# GPS_radiologger_v21_L70_CMWX.net
KiCad netlist of a schematic drawn in EAGLE
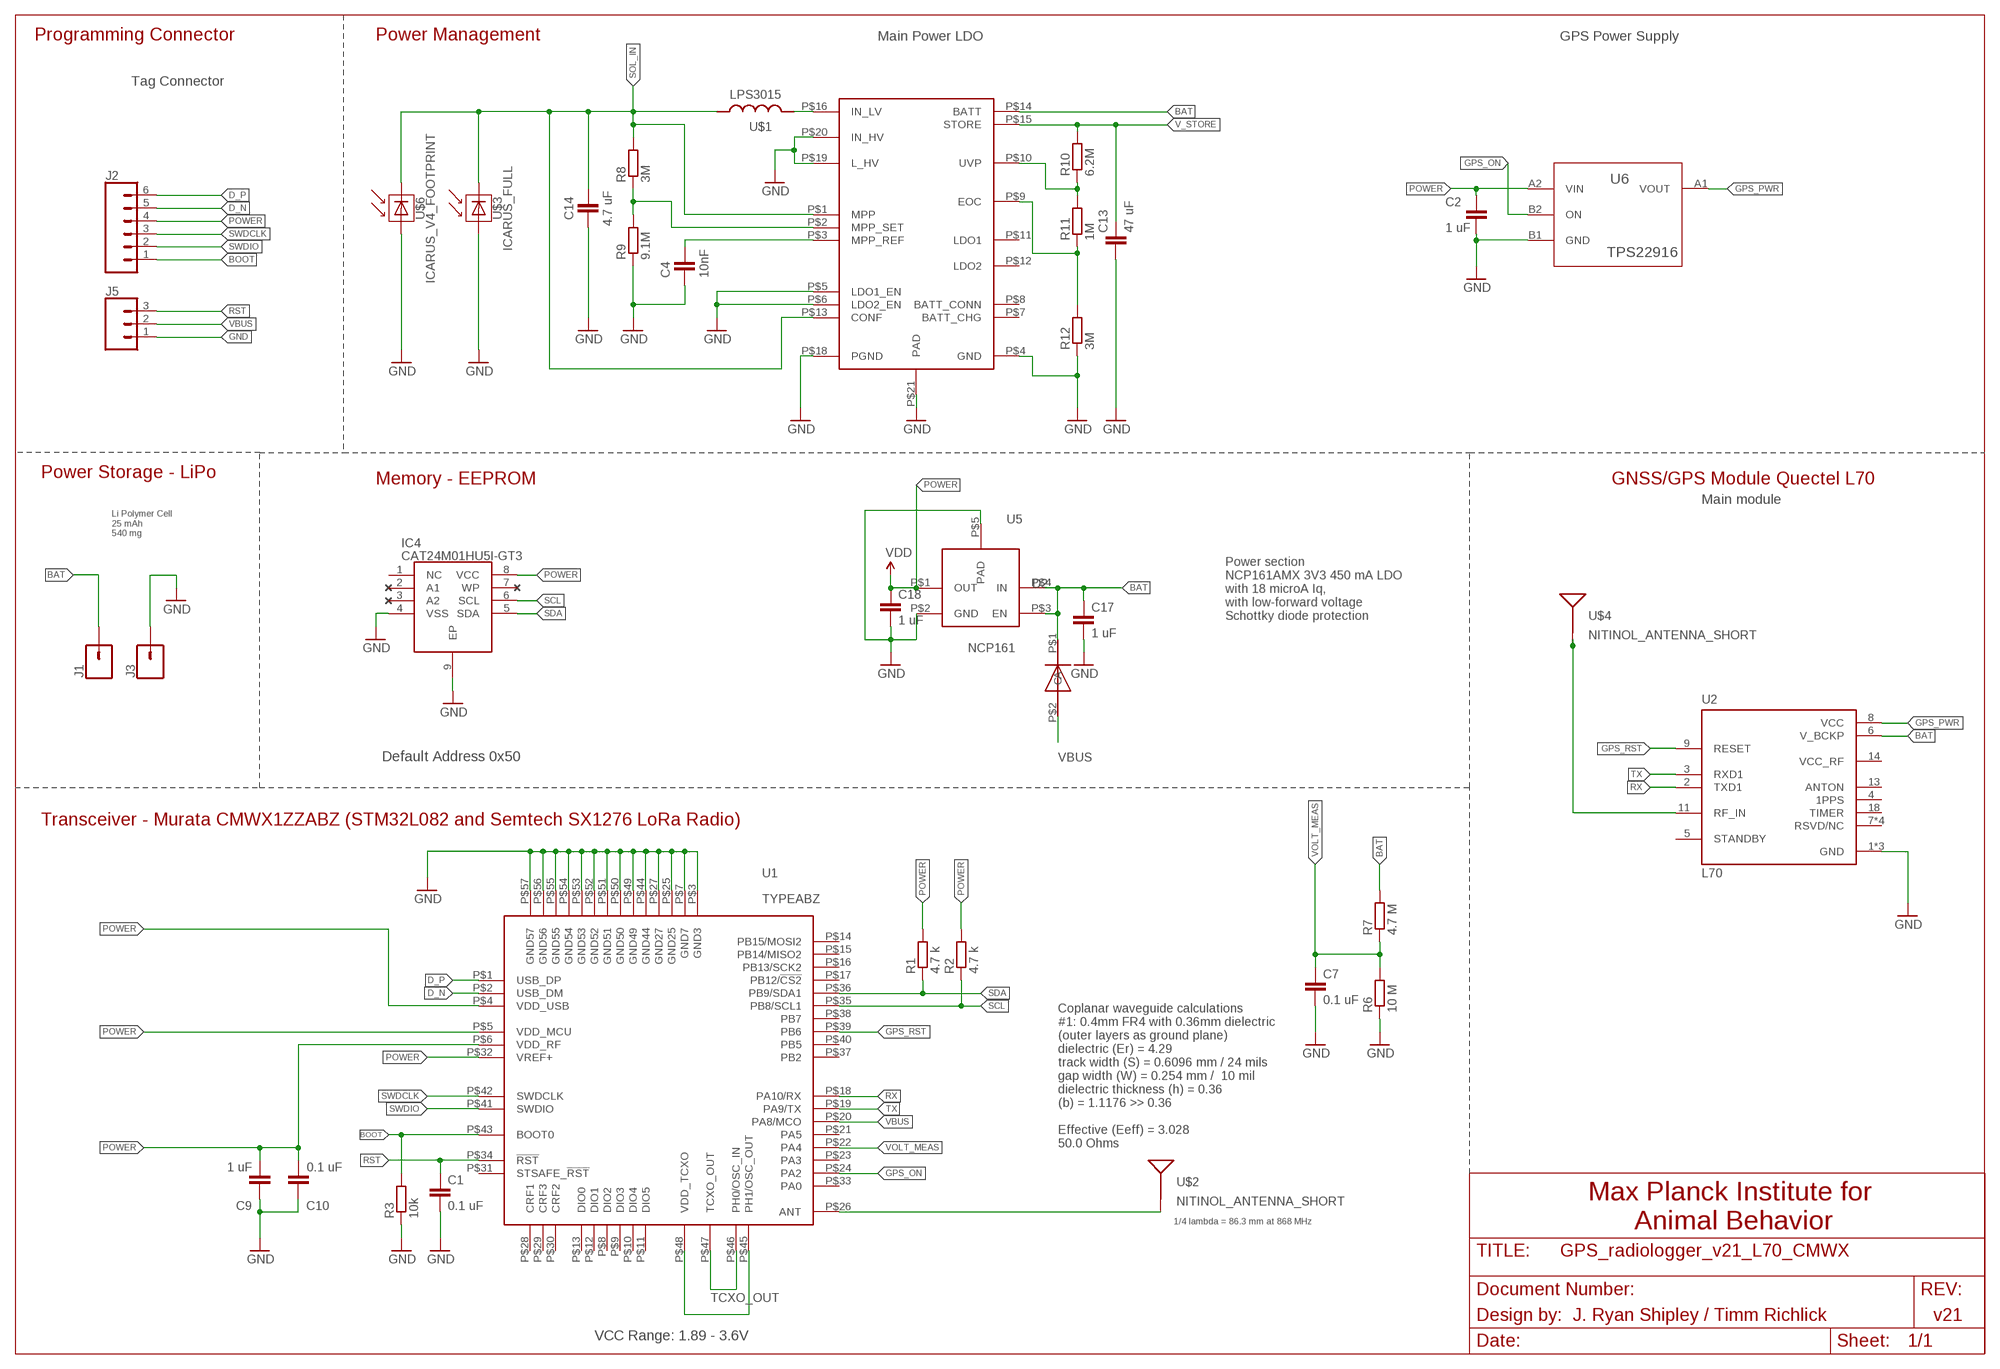
[diagram p0: schematic, sheet 1]

(export (version "E")
  (design (tool "Eeschema 10.0.6"))
  (components
    (comp (ref "C1")
      (value "0.1 uF")
      (footprint "eagle-import:C0201")
      (libsource (lib "eagle-import") (part "C-EUC0201"))
    )
    (comp (ref "C2")
      (value "1 uF")
      (footprint "eagle-import:C0201")
      (libsource (lib "eagle-import") (part "C-EUC0201"))
    )
    (comp (ref "C4")
      (value "10nF")
      (footprint "eagle-import:C0201")
      (libsource (lib "eagle-import") (part "C-EUC0201"))
    )
    (comp (ref "C7")
      (value "0.1 uF")
      (footprint "eagle-import:C0201")
      (libsource (lib "eagle-import") (part "C-EUC0201"))
    )
    (comp (ref "C9")
      (value "1 uF")
      (footprint "eagle-import:C0201")
      (libsource (lib "eagle-import") (part "C-EUC0201"))
    )
    (comp (ref "C10")
      (value "0.1 uF")
      (footprint "eagle-import:C0201")
      (libsource (lib "eagle-import") (part "C-EUC0201"))
    )
    (comp (ref "C13")
      (value "47 uF")
      (footprint "eagle-import:C0603")
      (libsource (lib "eagle-import") (part "C-EUC0603"))
    )
    (comp (ref "C14")
      (value "4.7 uF")
      (footprint "eagle-import:C0201")
      (libsource (lib "eagle-import") (part "C-EUC0201"))
    )
    (comp (ref "C17")
      (value "1 uF")
      (footprint "eagle-import:0402-CAP")
      (libsource (lib "eagle-import") (part "0402CAP.KW"))
    )
    (comp (ref "C18")
      (value "1 uF")
      (footprint "eagle-import:0402-CAP")
      (libsource (lib "eagle-import") (part "0402CAP.KW"))
    )
    (comp (ref "D2")
      (value "CDSQR4148-HF")
      (footprint "eagle-import:CDSQR4148-HF")
      (libsource (lib "eagle-import") (part "CDSQR4148-HF"))
    )
    (comp (ref "IC4")
      (value "CAT24M01HU5I-GT3")
      (footprint "eagle-import:SON50P300X200X55-9N")
      (fields
        (field (name "MOUSER_PART_NUMBER") "863-CAT24M01HU5I-GT3")
        (field (name "RS_PART_NUMBER") "7814831P")
      )
      (libsource (lib "eagle-import") (part "CAT24M01HU5I-GT3"))
    )
    (comp (ref "J1")
      (value "CONN_01PTH_NO_SILK_SMALL")
      (footprint "eagle-import:1X01_SMALL")
      (libsource (lib "eagle-import") (part "CONN_01PTH_NO_SILK_SMALL"))
    )
    (comp (ref "J2")
      (value "CONN_061.27MM")
      (footprint "eagle-import:1X06_1.27MM")
      (libsource (lib "eagle-import") (part "CONN_061.27MM"))
    )
    (comp (ref "J3")
      (value "CONN_01PTH_NO_SILK_SMALL")
      (footprint "eagle-import:1X01_SMALL")
      (libsource (lib "eagle-import") (part "CONN_01PTH_NO_SILK_SMALL"))
    )
    (comp (ref "J5")
      (value "CONN_031X03_1.27_NO_SILK")
      (footprint "eagle-import:1X03_1.27MM_NO_SILK")
      (libsource (lib "eagle-import") (part "CONN_031X03_1.27_NO_SILK"))
    )
    (comp (ref "R1")
      (value "4.7 k")
      (footprint "eagle-import:R0201")
      (libsource (lib "eagle-import") (part "R-EU_R0201"))
    )
    (comp (ref "R2")
      (value "4.7 k")
      (footprint "eagle-import:R0201")
      (libsource (lib "eagle-import") (part "R-EU_R0201"))
    )
    (comp (ref "R3")
      (value "10k")
      (footprint "eagle-import:R0201")
      (libsource (lib "eagle-import") (part "R-EU_R0201"))
    )
    (comp (ref "R6")
      (value "10 M")
      (footprint "eagle-import:R0201")
      (libsource (lib "eagle-import") (part "R-EU_R0201"))
    )
    (comp (ref "R7")
      (value "4.7 M")
      (footprint "eagle-import:R0201")
      (libsource (lib "eagle-import") (part "R-EU_R0201"))
    )
    (comp (ref "R8")
      (value "3M")
      (footprint "eagle-import:R0201")
      (libsource (lib "eagle-import") (part "R-EU_R0201"))
    )
    (comp (ref "R9")
      (value "9.1M")
      (footprint "eagle-import:R0201")
      (libsource (lib "eagle-import") (part "R-EU_R0201"))
    )
    (comp (ref "R10")
      (value "6.2M")
      (footprint "eagle-import:R0201")
      (libsource (lib "eagle-import") (part "R-EU_R0201"))
    )
    (comp (ref "R11")
      (value "1M")
      (footprint "eagle-import:R0201")
      (libsource (lib "eagle-import") (part "R-EU_R0201"))
    )
    (comp (ref "R12")
      (value "3M")
      (footprint "eagle-import:R0201")
      (libsource (lib "eagle-import") (part "R-EU_R0201"))
    )
    (comp (ref "U$1")
      (value "LPS3015")
      (footprint "eagle-import:LPS_3015")
      (libsource (lib "eagle-import") (part "LPS3015"))
    )
    (comp (ref "U$2")
      (value "NITINOL_ANTENNA_SHORT")
      (footprint "eagle-import:ICARUS_NITINOL_ANTENNA_SHORT")
      (libsource (lib "eagle-import") (part "NITINOL_ANTENNA_SHORT"))
    )
    (comp (ref "U$3")
      (value "ICARUS_FULL")
      (footprint "eagle-import:ICARUS_FULL")
      (libsource (lib "eagle-import") (part "ICARUS_FULL"))
    )
    (comp (ref "U$4")
      (value "NITINOL_ANTENNA_SHORT")
      (footprint "eagle-import:ICARUS_NITINOL_ANTENNA_SHORT")
      (libsource (lib "eagle-import") (part "NITINOL_ANTENNA_SHORT"))
    )
    (comp (ref "U$6")
      (value "ICARUS_V4_FOOTPRINT")
      (footprint "eagle-import:ICARUS_FULL_FOOTPRINT")
      (libsource (lib "eagle-import") (part "ICARUS_V4_FOOTPRINT"))
    )
    (comp (ref "U1")
      (value "TYPEABZ")
      (footprint "eagle-import:TYPEABZ")
      (libsource (lib "eagle-import") (part "TYPEABZ"))
    )
    (comp (ref "U2")
      (value "L70")
      (footprint "eagle-import:XCVR_L70")
      (fields (field (name "MF") "Quectel"))
      (libsource (lib "eagle-import") (part "L70"))
    )
    (comp (ref "U4")
      (value "SPV1050")
      (footprint "eagle-import:SPV1050")
      (libsource (lib "eagle-import") (part "SPV1050"))
    )
    (comp (ref "U5")
      (value "NCP161")
      (footprint "eagle-import:NCP161")
      (libsource (lib "eagle-import") (part "NCP161"))
    )
    (comp (ref "U6")
      (value "TPS22916")
      (footprint "eagle-import:TPS22916")
      (fields (field (name "MF") "Texas Instruments") (field (name "MP") "LP5900TL-3.0"))
      (libsource (lib "eagle-import") (part "TPS22916"))
    )
  )
  (nets
    (net (code "1") (name "/TCXO_OUT") (class "Default")
      (node (ref "U1") (pin "P$46") (pinfunction "PH0/OSC_IN_P$46") (pintype "bidirectional"))
      (node (ref "U1") (pin "P$47") (pinfunction "TCXO_OUT_P$47") (pintype "bidirectional"))
    )
    (net (code "2") (name "BAT") (class "Default")
      (node (ref "C17") (pin "1") (pinfunction "1_1") (pintype "passive"))
      (node (ref "D2") (pin "P$1") (pinfunction "C_P$1") (pintype "bidirectional"))
      (node (ref "J1") (pin "P$1") (pinfunction "1_P$1") (pintype "passive"))
      (node (ref "R7") (pin "2") (pinfunction "2_2") (pintype "passive"))
      (node (ref "U2") (pin "6") (pinfunction "V_BCKP_6") (pintype "power_in"))
      (node (ref "U4") (pin "P$14") (pinfunction "BATT_P$14") (pintype "bidirectional"))
      (node (ref "U5") (pin "P$3") (pinfunction "EN_P$3") (pintype "bidirectional"))
      (node (ref "U5") (pin "P$4") (pinfunction "IN_P$4") (pintype "power_in"))
    )
    (net (code "3") (name "BOOT") (class "Default")
      (node (ref "J2") (pin "1") (pinfunction "1_1") (pintype "passive"))
      (node (ref "R3") (pin "2") (pinfunction "2_2") (pintype "passive"))
      (node (ref "U1") (pin "P$43") (pinfunction "BOOT0_P$43") (pintype "bidirectional"))
    )
    (net (code "4") (name "D_N") (class "Default")
      (node (ref "J2") (pin "5") (pinfunction "5_5") (pintype "passive"))
      (node (ref "U1") (pin "P$2") (pinfunction "USB_DM_P$2") (pintype "bidirectional"))
    )
    (net (code "5") (name "D_P") (class "Default")
      (node (ref "J2") (pin "6") (pinfunction "6_6") (pintype "passive"))
      (node (ref "U1") (pin "P$1") (pinfunction "USB_DP_P$1") (pintype "bidirectional"))
    )
    (net (code "6") (name "GND") (class "Default")
      (node (ref "C1") (pin "2") (pinfunction "2_2") (pintype "passive"))
      (node (ref "C10") (pin "1") (pinfunction "1_1") (pintype "passive"))
      (node (ref "C13") (pin "2") (pinfunction "2_2") (pintype "passive"))
      (node (ref "C14") (pin "2") (pinfunction "2_2") (pintype "passive"))
      (node (ref "C17") (pin "2") (pinfunction "2_2") (pintype "passive"))
      (node (ref "C18") (pin "2") (pinfunction "2_2") (pintype "passive"))
      (node (ref "C2") (pin "2") (pinfunction "2_2") (pintype "passive"))
      (node (ref "C4") (pin "2") (pinfunction "2_2") (pintype "passive"))
      (node (ref "C7") (pin "2") (pinfunction "2_2") (pintype "passive"))
      (node (ref "C9") (pin "1") (pinfunction "1_1") (pintype "passive"))
      (node (ref "IC4") (pin "4") (pinfunction "VSS_4") (pintype "power_in"))
      (node (ref "IC4") (pin "9") (pinfunction "EP_9") (pintype "bidirectional"))
      (node (ref "J3") (pin "P$1") (pinfunction "1_P$1") (pintype "passive"))
      (node (ref "J5") (pin "1") (pinfunction "1_1") (pintype "passive"))
      (node (ref "R12") (pin "1") (pinfunction "1_1") (pintype "passive"))
      (node (ref "R3") (pin "1") (pinfunction "1_1") (pintype "passive"))
      (node (ref "R6") (pin "1") (pinfunction "1_1") (pintype "passive"))
      (node (ref "R9") (pin "1") (pinfunction "1_1") (pintype "passive"))
      (node (ref "U$3") (pin "P$2") (pinfunction "MINUS_P$2") (pintype "passive"))
      (node (ref "U$6") (pin "P$3") (pinfunction "MINUS_P$3") (pintype "passive"))
      (node (ref "U1") (pin "P$25") (pinfunction "GND25_P$25") (pintype "power_in"))
      (node (ref "U1") (pin "P$27") (pinfunction "GND27_P$27") (pintype "power_in"))
      (node (ref "U1") (pin "P$3") (pinfunction "GND3_P$3") (pintype "power_in"))
      (node (ref "U1") (pin "P$44") (pinfunction "GND44_P$44") (pintype "power_in"))
      (node (ref "U1") (pin "P$49") (pinfunction "GND49_P$49") (pintype "power_in"))
      (node (ref "U1") (pin "P$50") (pinfunction "GND50_P$50") (pintype "power_in"))
      (node (ref "U1") (pin "P$51") (pinfunction "GND51_P$51") (pintype "power_in"))
      (node (ref "U1") (pin "P$52") (pinfunction "GND52_P$52") (pintype "power_in"))
      (node (ref "U1") (pin "P$53") (pinfunction "GND53_P$53") (pintype "power_in"))
      (node (ref "U1") (pin "P$54") (pinfunction "GND54_P$54") (pintype "power_in"))
      (node (ref "U1") (pin "P$55") (pinfunction "GND55_P$55") (pintype "power_in"))
      (node (ref "U1") (pin "P$56") (pinfunction "GND56_P$56") (pintype "power_in"))
      (node (ref "U1") (pin "P$57") (pinfunction "GND57_P$57") (pintype "power_in"))
      (node (ref "U1") (pin "P$7") (pinfunction "GND7_P$7") (pintype "power_in"))
      (node (ref "U2") (pin "1") (pinfunction "GND_1") (pintype "power_in"))
      (node (ref "U2") (pin "10") (pinfunction "GND_10") (pintype "power_in"))
      (node (ref "U2") (pin "12") (pinfunction "GND_12") (pintype "power_in"))
      (node (ref "U4") (pin "P$18") (pinfunction "PGND_P$18") (pintype "power_in"))
      (node (ref "U4") (pin "P$19") (pinfunction "L_HV_P$19") (pintype "power_in"))
      (node (ref "U4") (pin "P$20") (pinfunction "IN_HV_P$20") (pintype "power_in"))
      (node (ref "U4") (pin "P$21") (pinfunction "PAD_P$21") (pintype "power_in"))
      (node (ref "U4") (pin "P$4") (pinfunction "GND_P$4") (pintype "power_in"))
      (node (ref "U4") (pin "P$5") (pinfunction "LDO1_EN_P$5") (pintype "input"))
      (node (ref "U4") (pin "P$6") (pinfunction "LDO2_EN_P$6") (pintype "input"))
      (node (ref "U5") (pin "P$2") (pinfunction "GND_P$2") (pintype "power_in"))
      (node (ref "U5") (pin "P$5") (pinfunction "PAD_P$5") (pintype "power_in"))
      (node (ref "U6") (pin "B1") (pinfunction "GND_B1") (pintype "passive"))
    )
    (net (code "7") (name "GPS_ON") (class "Default")
      (node (ref "U1") (pin "P$24") (pinfunction "PA2_P$24") (pintype "bidirectional"))
      (node (ref "U6") (pin "B2") (pinfunction "ON_B2") (pintype "input"))
    )
    (net (code "8") (name "GPS_PWR") (class "Default")
      (node (ref "U2") (pin "8") (pinfunction "VCC_8") (pintype "power_in"))
      (node (ref "U6") (pin "A1") (pinfunction "VOUT_A1") (pintype "output"))
    )
    (net (code "9") (name "GPS_RST") (class "Default")
      (node (ref "U1") (pin "P$39") (pinfunction "PB6_P$39") (pintype "bidirectional"))
      (node (ref "U2") (pin "9") (pinfunction "RESET_9") (pintype "input"))
    )
    (net (code "10") (name "Net-(U$1-2)") (class "Default")
      (node (ref "U$1") (pin "P$2") (pinfunction "2_P$2") (pintype "passive"))
      (node (ref "U4") (pin "P$16") (pinfunction "IN_LV_P$16") (pintype "power_in"))
    )
    (net (code "11") (name "Net-(U1-ANT)") (class "Default")
      (node (ref "U$2") (pin "1") (pinfunction "SIGNAL_1") (pintype "bidirectional"))
      (node (ref "U$2") (pin "2") (pinfunction "SIGNAL_2") (pintype "bidirectional"))
      (node (ref "U$2") (pin "3") (pinfunction "SIGNAL_3") (pintype "bidirectional"))
      (node (ref "U1") (pin "P$26") (pinfunction "ANT_P$26") (pintype "bidirectional"))
    )
    (net (code "12") (name "Net-(U1-PH1{slash}OSC_OUT)") (class "Default")
      (node (ref "U1") (pin "P$45") (pinfunction "PH1/OSC_OUT_P$45") (pintype "bidirectional"))
      (node (ref "U1") (pin "P$48") (pinfunction "VDD_TCXO_P$48") (pintype "power_in"))
    )
    (net (code "13") (name "Net-(U2-RF_IN)") (class "Default")
      (node (ref "U$4") (pin "1") (pinfunction "SIGNAL_1") (pintype "bidirectional"))
      (node (ref "U$4") (pin "2") (pinfunction "SIGNAL_2") (pintype "bidirectional"))
      (node (ref "U$4") (pin "3") (pinfunction "SIGNAL_3") (pintype "bidirectional"))
      (node (ref "U2") (pin "11") (pinfunction "RF_IN_11") (pintype "input"))
    )
    (net (code "14") (name "Net-(U4-EOC)") (class "Default")
      (node (ref "R11") (pin "1") (pinfunction "1_1") (pintype "passive"))
      (node (ref "R12") (pin "2") (pinfunction "2_2") (pintype "passive"))
      (node (ref "U4") (pin "P$9") (pinfunction "EOC_P$9") (pintype "input"))
    )
    (net (code "15") (name "Net-(U4-MPP_REF)") (class "Default")
      (node (ref "C4") (pin "1") (pinfunction "1_1") (pintype "passive"))
      (node (ref "U4") (pin "P$3") (pinfunction "MPP_REF_P$3") (pintype "input"))
    )
    (net (code "16") (name "Net-(U4-MPP_SET)") (class "Default")
      (node (ref "R8") (pin "1") (pinfunction "1_1") (pintype "passive"))
      (node (ref "R9") (pin "2") (pinfunction "2_2") (pintype "passive"))
      (node (ref "U4") (pin "P$2") (pinfunction "MPP_SET_P$2") (pintype "input"))
    )
    (net (code "17") (name "Net-(U4-UVP)") (class "Default")
      (node (ref "R10") (pin "1") (pinfunction "1_1") (pintype "passive"))
      (node (ref "R11") (pin "2") (pinfunction "2_2") (pintype "passive"))
      (node (ref "U4") (pin "P$10") (pinfunction "UVP_P$10") (pintype "input"))
    )
    (net (code "18") (name "POWER") (class "Default")
      (node (ref "C10") (pin "2") (pinfunction "2_2") (pintype "passive"))
      (node (ref "C18") (pin "1") (pinfunction "1_1") (pintype "passive"))
      (node (ref "C2") (pin "1") (pinfunction "1_1") (pintype "passive"))
      (node (ref "C9") (pin "2") (pinfunction "2_2") (pintype "passive"))
      (node (ref "IC4") (pin "8") (pinfunction "VCC_8") (pintype "power_in"))
      (node (ref "J2") (pin "4") (pinfunction "4_4") (pintype "passive"))
      (node (ref "R1") (pin "2") (pinfunction "2_2") (pintype "passive"))
      (node (ref "R2") (pin "2") (pinfunction "2_2") (pintype "passive"))
      (node (ref "U1") (pin "P$32") (pinfunction "VREF+_P$32") (pintype "power_in"))
      (node (ref "U1") (pin "P$4") (pinfunction "VDD_USB_P$4") (pintype "power_in"))
      (node (ref "U1") (pin "P$5") (pinfunction "VDD_MCU_P$5") (pintype "power_in"))
      (node (ref "U1") (pin "P$6") (pinfunction "VDD_RF_P$6") (pintype "power_in"))
      (node (ref "U5") (pin "P$1") (pinfunction "OUT_P$1") (pintype "power_in"))
      (node (ref "U6") (pin "A2") (pinfunction "VIN_A2") (pintype "power_in"))
    )
    (net (code "19") (name "RST") (class "Default")
      (node (ref "C1") (pin "1") (pinfunction "1_1") (pintype "passive"))
      (node (ref "J5") (pin "3") (pinfunction "3_3") (pintype "passive"))
      (node (ref "U1") (pin "P$34") (pinfunction "~{RST}_P$34") (pintype "bidirectional"))
    )
    (net (code "20") (name "RX") (class "Default")
      (node (ref "U1") (pin "P$18") (pinfunction "PA10/RX_P$18") (pintype "bidirectional"))
      (node (ref "U2") (pin "2") (pinfunction "TXD1_2") (pintype "output"))
    )
    (net (code "21") (name "SCL") (class "Default")
      (node (ref "IC4") (pin "6") (pinfunction "SCL_6") (pintype "bidirectional"))
      (node (ref "R2") (pin "1") (pinfunction "1_1") (pintype "passive"))
      (node (ref "U1") (pin "P$35") (pinfunction "PB8/SCL1_P$35") (pintype "bidirectional"))
    )
    (net (code "22") (name "SDA") (class "Default")
      (node (ref "IC4") (pin "5") (pinfunction "SDA_5") (pintype "bidirectional"))
      (node (ref "R1") (pin "1") (pinfunction "1_1") (pintype "passive"))
      (node (ref "U1") (pin "P$36") (pinfunction "PB9/SDA1_P$36") (pintype "bidirectional"))
    )
    (net (code "23") (name "SOL_IN") (class "Default")
      (node (ref "C14") (pin "1") (pinfunction "1_1") (pintype "passive"))
      (node (ref "R8") (pin "2") (pinfunction "2_2") (pintype "passive"))
      (node (ref "U$1") (pin "P$1") (pinfunction "1_P$1") (pintype "passive"))
      (node (ref "U$3") (pin "P$1") (pinfunction "PLUS_P$1") (pintype "passive"))
      (node (ref "U$6") (pin "P$1") (pinfunction "PLUS_P$1") (pintype "passive"))
      (node (ref "U4") (pin "P$1") (pinfunction "MPP_P$1") (pintype "input"))
      (node (ref "U4") (pin "P$13") (pinfunction "CONF_P$13") (pintype "input"))
    )
    (net (code "24") (name "SWDCLK") (class "Default")
      (node (ref "J2") (pin "3") (pinfunction "3_3") (pintype "passive"))
      (node (ref "U1") (pin "P$42") (pinfunction "SWDCLK_P$42") (pintype "bidirectional"))
    )
    (net (code "25") (name "SWDIO") (class "Default")
      (node (ref "J2") (pin "2") (pinfunction "2_2") (pintype "passive"))
      (node (ref "U1") (pin "P$41") (pinfunction "SWDIO_P$41") (pintype "bidirectional"))
    )
    (net (code "26") (name "TX") (class "Default")
      (node (ref "U1") (pin "P$19") (pinfunction "PA9/TX_P$19") (pintype "bidirectional"))
      (node (ref "U2") (pin "3") (pinfunction "RXD1_3") (pintype "input"))
    )
    (net (code "27") (name "VBUS") (class "Default")
      (node (ref "D2") (pin "P$2") (pinfunction "A_P$2") (pintype "bidirectional"))
      (node (ref "J5") (pin "2") (pinfunction "2_2") (pintype "passive"))
      (node (ref "U1") (pin "P$20") (pinfunction "PA8/MCO_P$20") (pintype "bidirectional"))
    )
    (net (code "28") (name "VOLT_MEAS") (class "Default")
      (node (ref "C7") (pin "1") (pinfunction "1_1") (pintype "passive"))
      (node (ref "R6") (pin "2") (pinfunction "2_2") (pintype "passive"))
      (node (ref "R7") (pin "1") (pinfunction "1_1") (pintype "passive"))
      (node (ref "U1") (pin "P$22") (pinfunction "PA4_P$22") (pintype "bidirectional"))
    )
    (net (code "29") (name "V_STORE") (class "Default")
      (node (ref "C13") (pin "1") (pinfunction "1_1") (pintype "passive"))
      (node (ref "R10") (pin "2") (pinfunction "2_2") (pintype "passive"))
      (node (ref "U4") (pin "P$15") (pinfunction "STORE_P$15") (pintype "bidirectional"))
    )
    (net (code "30") (name "unconnected-(IC4-A1-Pad2)") (class "Default")
      (node (ref "IC4") (pin "2") (pinfunction "A1_2") (pintype "bidirectional"))
    )
    (net (code "31") (name "unconnected-(IC4-A2-Pad3)") (class "Default")
      (node (ref "IC4") (pin "3") (pinfunction "A2_3") (pintype "bidirectional"))
    )
    (net (code "32") (name "unconnected-(IC4-NC-Pad1)") (class "Default")
      (node (ref "IC4") (pin "1") (pinfunction "NC_1") (pintype "no_connect"))
    )
    (net (code "33") (name "unconnected-(IC4-WP-Pad7)") (class "Default")
      (node (ref "IC4") (pin "7") (pinfunction "WP_7") (pintype "bidirectional"))
    )
    (net (code "34") (name "unconnected-(U1-CRF1-PadP$28)") (class "Default")
      (node (ref "U1") (pin "P$28") (pinfunction "CRF1_P$28") (pintype "no_connect"))
    )
    (net (code "35") (name "unconnected-(U1-CRF2-PadP$30)") (class "Default")
      (node (ref "U1") (pin "P$30") (pinfunction "CRF2_P$30") (pintype "no_connect"))
    )
    (net (code "36") (name "unconnected-(U1-CRF3-PadP$29)") (class "Default")
      (node (ref "U1") (pin "P$29") (pinfunction "CRF3_P$29") (pintype "no_connect"))
    )
    (net (code "37") (name "unconnected-(U1-DIO0-PadP$13)") (class "Default")
      (node (ref "U1") (pin "P$13") (pinfunction "DIO0_P$13") (pintype "no_connect"))
    )
    (net (code "38") (name "unconnected-(U1-DIO1-PadP$12)") (class "Default")
      (node (ref "U1") (pin "P$12") (pinfunction "DIO1_P$12") (pintype "no_connect"))
    )
    (net (code "39") (name "unconnected-(U1-DIO2-PadP$8)") (class "Default")
      (node (ref "U1") (pin "P$8") (pinfunction "DIO2_P$8") (pintype "no_connect"))
    )
    (net (code "40") (name "unconnected-(U1-DIO3-PadP$9)") (class "Default")
      (node (ref "U1") (pin "P$9") (pinfunction "DIO3_P$9") (pintype "no_connect"))
    )
    (net (code "41") (name "unconnected-(U1-DIO4-PadP$10)") (class "Default")
      (node (ref "U1") (pin "P$10") (pinfunction "DIO4_P$10") (pintype "bidirectional"))
    )
    (net (code "42") (name "unconnected-(U1-DIO5-PadP$11)") (class "Default")
      (node (ref "U1") (pin "P$11") (pinfunction "DIO5_P$11") (pintype "bidirectional"))
    )
    (net (code "43") (name "unconnected-(U1-PA0-PadP$33)") (class "Default")
      (node (ref "U1") (pin "P$33") (pinfunction "PA0_P$33") (pintype "bidirectional"))
    )
    (net (code "44") (name "unconnected-(U1-PA3-PadP$23)") (class "Default")
      (node (ref "U1") (pin "P$23") (pinfunction "PA3_P$23") (pintype "bidirectional"))
    )
    (net (code "45") (name "unconnected-(U1-PA5-PadP$21)") (class "Default")
      (node (ref "U1") (pin "P$21") (pinfunction "PA5_P$21") (pintype "bidirectional"))
    )
    (net (code "46") (name "unconnected-(U1-PB2-PadP$37)") (class "Default")
      (node (ref "U1") (pin "P$37") (pinfunction "PB2_P$37") (pintype "bidirectional"))
    )
    (net (code "47") (name "unconnected-(U1-PB5-PadP$40)") (class "Default")
      (node (ref "U1") (pin "P$40") (pinfunction "PB5_P$40") (pintype "bidirectional"))
    )
    (net (code "48") (name "unconnected-(U1-PB7-PadP$38)") (class "Default")
      (node (ref "U1") (pin "P$38") (pinfunction "PB7_P$38") (pintype "bidirectional"))
    )
    (net (code "49") (name "unconnected-(U1-PB12{slash}~{CS2}-PadP$17)") (class "Default")
      (node (ref "U1") (pin "P$17") (pinfunction "PB12/~{CS2}_P$17") (pintype "bidirectional"))
    )
    (net (code "50") (name "unconnected-(U1-PB13{slash}SCK2-PadP$16)") (class "Default")
      (node (ref "U1") (pin "P$16") (pinfunction "PB13/SCK2_P$16") (pintype "bidirectional"))
    )
    (net (code "51") (name "unconnected-(U1-PB14{slash}MISO2-PadP$15)") (class "Default")
      (node (ref "U1") (pin "P$15") (pinfunction "PB14/MISO2_P$15") (pintype "bidirectional"))
    )
    (net (code "52") (name "unconnected-(U1-PB15{slash}MOSI2-PadP$14)") (class "Default")
      (node (ref "U1") (pin "P$14") (pinfunction "PB15/MOSI2_P$14") (pintype "bidirectional"))
    )
    (net (code "53") (name "unconnected-(U1-STSAFE_~{RST}-PadP$31)") (class "Default")
      (node (ref "U1") (pin "P$31") (pinfunction "STSAFE_~{RST}_P$31") (pintype "bidirectional"))
    )
    (net (code "54") (name "unconnected-(U2-1PPS-Pad4)") (class "Default")
      (node (ref "U2") (pin "4") (pinfunction "1PPS_4") (pintype "output"))
    )
    (net (code "55") (name "unconnected-(U2-ANTON-Pad13)") (class "Default")
      (node (ref "U2") (pin "13") (pinfunction "ANTON_13") (pintype "output"))
    )
    (net (code "56") (name "unconnected-(U2-RSVD{slash}NC-Pad7)") (class "Default")
      (node (ref "U2") (pin "7") (pinfunction "RSVD/NC_7") (pintype "no_connect"))
    )
    (net (code "57") (name "unconnected-(U2-RSVD{slash}NC-Pad15)") (class "Default")
      (node (ref "U2") (pin "15") (pinfunction "RSVD/NC_15") (pintype "no_connect"))
    )
    (net (code "58") (name "unconnected-(U2-RSVD{slash}NC-Pad16)") (class "Default")
      (node (ref "U2") (pin "16") (pinfunction "RSVD/NC_16") (pintype "no_connect"))
    )
    (net (code "59") (name "unconnected-(U2-RSVD{slash}NC-Pad17)") (class "Default")
      (node (ref "U2") (pin "17") (pinfunction "RSVD/NC_17") (pintype "no_connect"))
    )
    (net (code "60") (name "unconnected-(U2-STANDBY-Pad5)") (class "Default")
      (node (ref "U2") (pin "5") (pinfunction "STANDBY_5") (pintype "input"))
    )
    (net (code "61") (name "unconnected-(U2-TIMER-Pad18)") (class "Default")
      (node (ref "U2") (pin "18") (pinfunction "TIMER_18") (pintype "output"))
    )
    (net (code "62") (name "unconnected-(U2-VCC_RF-Pad14)") (class "Default")
      (node (ref "U2") (pin "14") (pinfunction "VCC_RF_14") (pintype "output"))
    )
    (net (code "63") (name "unconnected-(U4-BATT_CHG-PadP$7)") (class "Default")
      (node (ref "U4") (pin "P$7") (pinfunction "BATT_CHG_P$7") (pintype "open_collector"))
    )
    (net (code "64") (name "unconnected-(U4-BATT_CONN-PadP$8)") (class "Default")
      (node (ref "U4") (pin "P$8") (pinfunction "BATT_CONN_P$8") (pintype "open_collector"))
    )
    (net (code "65") (name "unconnected-(U4-LDO1-PadP$11)") (class "Default")
      (node (ref "U4") (pin "P$11") (pinfunction "LDO1_P$11") (pintype "output"))
    )
    (net (code "66") (name "unconnected-(U4-LDO2-PadP$12)") (class "Default")
      (node (ref "U4") (pin "P$12") (pinfunction "LDO2_P$12") (pintype "output"))
    )
  )
)
